# 02-MCU.net
KiCad netlist of a schematic drawn in Altium Designer
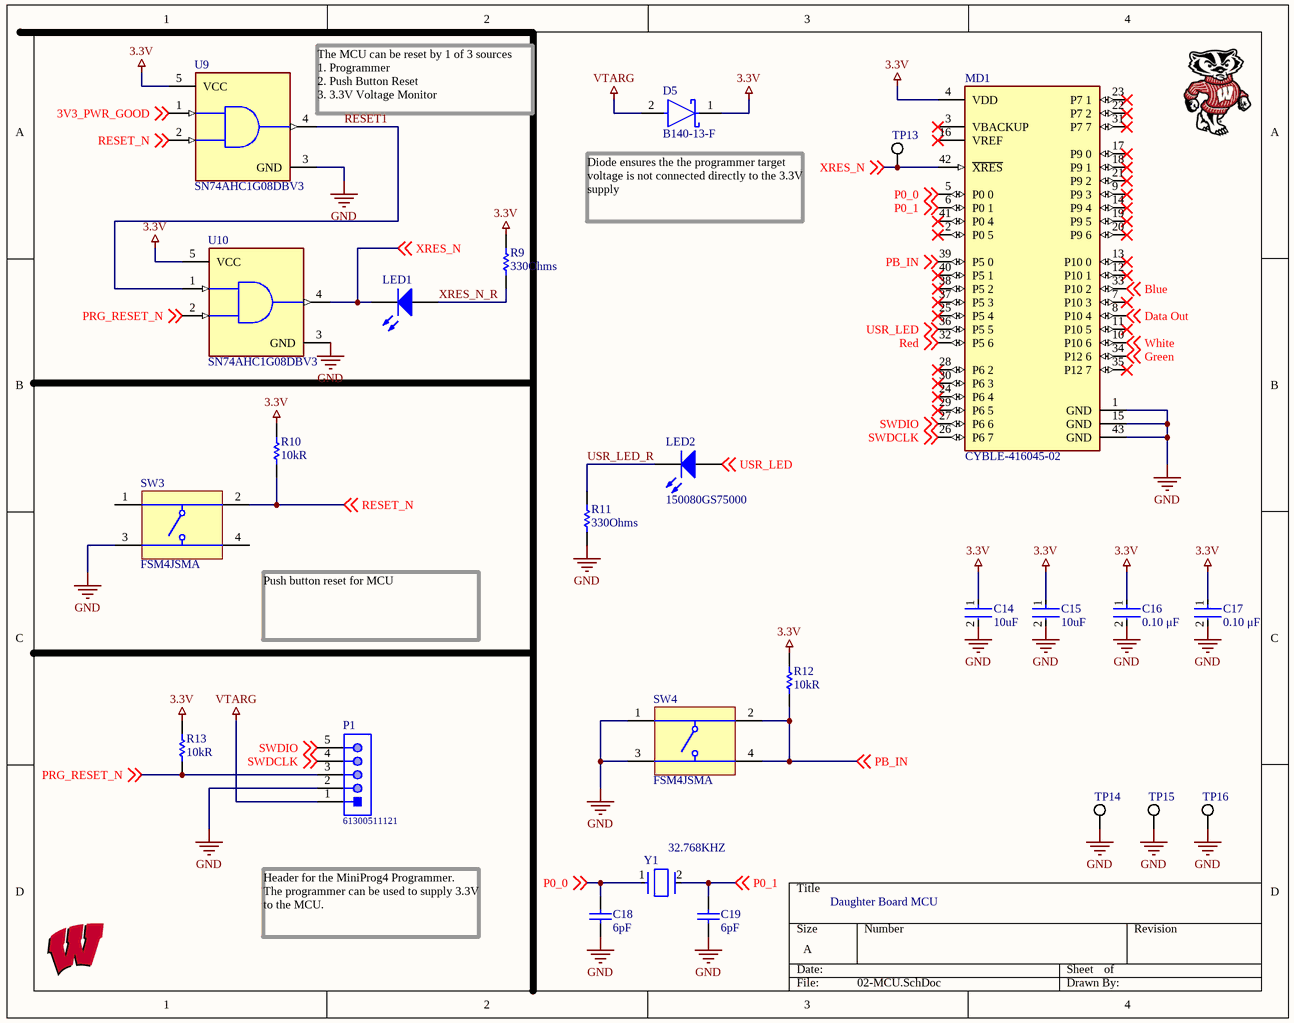
[diagram p0: 02-MCU.SchDoc]

(export (version "E")
  (design (tool "Eeschema 10.0.6"))
  (components
    (comp (ref "C14")
      (value "10uF")
      (footprint "FP-C0805C-DG-MFG")
      (description "CAP CER 10UF 10V X5R 0805")
      (fields (field (name "TOLERANCE") "10%") (field (name "MANUFACTURER PART NUMBER") "C0805C106K8PACTU"))
      (libsource (lib "Altium Content Vault") (part "11868f565c42a9108669ba33697ecf6"))
    )
    (comp (ref "C15")
      (value "10uF")
      (footprint "FP-C0805C-DG-MFG")
      (description "CAP CER 10UF 10V X5R 0805")
      (fields (field (name "TOLERANCE") "10%") (field (name "MANUFACTURER PART NUMBER") "C0805C106K8PACTU"))
      (libsource (lib "Altium Content Vault") (part "11868f565c42a9108669ba33697ecf6"))
    )
    (comp (ref "C16")
      (value "0.10 μF")
      (footprint "FP-C0805C-DN-MFG")
      (description "CAP CER 0.1UF 50V X7R 0805")
      (fields
        (field (name "MANUFACTURER PART NUMBER") "C0805C104K5RACTU")
        (field (name "MANUFACTURER") "KEMET")
      )
      (libsource (lib "Altium Content Vault") (part "b4654b650e69147ec39a6b967a45e02"))
    )
    (comp (ref "C17")
      (value "0.10 μF")
      (footprint "FP-C0805C-DN-MFG")
      (description "CAP CER 0.1UF 50V X7R 0805")
      (fields
        (field (name "MANUFACTURER PART NUMBER") "C0805C104K5RACTU")
        (field (name "MANUFACTURER") "KEMET")
      )
      (libsource (lib "Altium Content Vault") (part "b4654b650e69147ec39a6b967a45e02"))
    )
    (comp (ref "C18")
      (value "08055A6R0CAT2A")
      (footprint "CAPC2013X94X50LL20T25")
      (fields (field (name "MANUFACTURER") "AVX Interconnect / Elco") (field (name "CAPACITANCE") "6pF"))
      (libsource (lib "Altium Content Vault") (part "CAP"))
    )
    (comp (ref "C19")
      (value "08055A6R0CAT2A")
      (footprint "CAPC2013X94X50LL20T25")
      (fields (field (name "MANUFACTURER") "AVX Interconnect / Elco") (field (name "CAPACITANCE") "6pF"))
      (libsource (lib "Altium Content Vault") (part "CAP"))
    )
    (comp (ref "D5")
      (value "B140-13-F")
      (footprint "FP-SMA-MFG")
      (description "DIODE SCHOTTKY 40V 1A SMA")
      (libsource (lib "Altium Content Vault") (part "1d6ec82d83fb6aee721767c19dac4b9"))
    )
    (comp (ref "LED1")
      (value "150080RS75000")
      (footprint "0805_A")
      (description "SMD mono-color Chip LED, WL-SMCW, Red")
      (fields (field (name "MANUFACTURER") "Wuerth Elektronik"))
      (libsource (lib "Altium Content Vault") (part "WE-LED_K1A2-2"))
    )
    (comp (ref "LED2")
      (value "150080GS75000")
      (footprint "0805_A")
      (description "SMD mono-color Chip LED, WL-SMCW, Green")
      (fields (field (name "MANUFACTURER") "Wuerth Elektronik"))
      (libsource (lib "Altium Content Vault") (part "WE-LED_K1A2-2"))
    )
    (comp (ref "MD1")
      (value "CYBLE-416045-02")
      (footprint "FP-CYBLE-416045-02-MFG")
      (description "RF TXRX MOD BLUETOOTH TRACE ANT")
      (fields
        (field (name "OCTOPART") "https://octopart.com/cyble-416045-02-cypress+semiconductor-96386825")
        (field (name "MANUFACTURER") "Cypress Semiconductor")
      )
      (libsource (lib "Altium Content Vault") (part "10a29a4e77099fbb6f911efb04878b1"))
    )
    (comp (ref "P1")
      (value "61300511121")
      (footprint "61300511121")
      (description "THT Vertical Pin Header WR-PHD, Pitch 2.54 mm, Single Row, 5 pins")
      (fields (field (name "MANUFACTURER") "Wurth Elektronik") (field (name "PUBLISHER") "WurthElektronik"))
      (libsource (lib "Altium Content Vault") (part "WE-CN-1P-M-R5"))
    )
    (comp (ref "R9")
      (value "RC0805FR-07330RL")
      (footprint "RESC2013X60X35LL10T20")
      (description "Chip Resistor, 330 Ohm, +/- 1%, 125 mW, -55 to 155 degC, 0805 (2012 Metric), RoHS, Tape and Reel")
      (fields
        (field (name "MANUFACTURER") "Yageo")
        (field (name "TOLERANCE") "1%")
        (field (name "RESISTANCE") "330Ohms")
      )
      (libsource (lib "Altium Content Vault") (part "RES-2"))
    )
    (comp (ref "R10")
      (value "RC0805FR-0710KL")
      (footprint "RESC2013X60X35NL10T20")
      (description "Chip Resistor, 10 KOhm, +/- 1%, 0.125 W, -55 to 155 degC, 0805 (2012 Metric), RoHS, Tape and Reel")
      (fields
        (field (name "MANUFACTURER") "Yageo")
        (field (name "RESISTANCE") "10kR")
        (field (name "TOLERANCE") "1%")
      )
      (libsource (lib "Altium Content Vault") (part "RES-2"))
    )
    (comp (ref "R11")
      (value "RC0805FR-07330RL")
      (footprint "RESC2013X60X35LL10T20")
      (description "Chip Resistor, 330 Ohm, +/- 1%, 125 mW, -55 to 155 degC, 0805 (2012 Metric), RoHS, Tape and Reel")
      (fields
        (field (name "MANUFACTURER") "Yageo")
        (field (name "TOLERANCE") "1%")
        (field (name "RESISTANCE") "330Ohms")
      )
      (libsource (lib "Altium Content Vault") (part "RES-2"))
    )
    (comp (ref "R12")
      (value "RC0805FR-0710KL")
      (footprint "RESC2013X60X35NL10T20")
      (description "Chip Resistor, 10 KOhm, +/- 1%, 0.125 W, -55 to 155 degC, 0805 (2012 Metric), RoHS, Tape and Reel")
      (fields
        (field (name "MANUFACTURER") "Yageo")
        (field (name "RESISTANCE") "10kR")
        (field (name "TOLERANCE") "1%")
      )
      (libsource (lib "Altium Content Vault") (part "RES-2"))
    )
    (comp (ref "R13")
      (value "RC0805FR-0710KL")
      (footprint "RESC2013X60X35NL10T20")
      (description "Chip Resistor, 10 KOhm, +/- 1%, 0.125 W, -55 to 155 degC, 0805 (2012 Metric), RoHS, Tape and Reel")
      (fields
        (field (name "MANUFACTURER") "Yageo")
        (field (name "RESISTANCE") "10kR")
        (field (name "TOLERANCE") "1%")
      )
      (libsource (lib "Altium Content Vault") (part "RES-2"))
    )
    (comp (ref "SW3")
      (value "FSM4JSMA")
      (footprint "TECO-FSM4JSMA_V")
      (description "Swicth, SPST, 24 V, -35 to 85 degC, 4-Pin SMD, RoHS, Tape and Reel")
      (fields (field (name "MANUFACTURER") "TE Connectivity"))
      (libsource (lib "Altium Content Vault") (part "SW-SPST-4_A"))
    )
    (comp (ref "SW4")
      (value "FSM4JSMA")
      (footprint "TECO-FSM4JSMA_V")
      (description "Swicth, SPST, 24 V, -35 to 85 degC, 4-Pin SMD, RoHS, Tape and Reel")
      (fields (field (name "MANUFACTURER") "TE Connectivity"))
      (libsource (lib "Altium Content Vault") (part "SW-SPST-4_A"))
    )
    (comp (ref "TP13")
      (value "5019")
      (footprint "KSTN-5019_V")
      (description "Test Point, 1 Position SMD, RoHS, Tape and Reel")
      (libsource (lib "Altium Content Vault") (part "TESTPOINT_WHITE"))
    )
    (comp (ref "TP14")
      (value "5019")
      (footprint "KSTN-5019_V")
      (description "Test Point, 1 Position SMD, RoHS, Tape and Reel")
      (libsource (lib "Altium Content Vault") (part "TESTPOINT_WHITE"))
    )
    (comp (ref "TP15")
      (value "5019")
      (footprint "KSTN-5019_V")
      (description "Test Point, 1 Position SMD, RoHS, Tape and Reel")
      (libsource (lib "Altium Content Vault") (part "TESTPOINT_WHITE"))
    )
    (comp (ref "TP16")
      (value "5019")
      (footprint "KSTN-5019_V")
      (description "Test Point, 1 Position SMD, RoHS, Tape and Reel")
      (libsource (lib "Altium Content Vault") (part "TESTPOINT_WHITE"))
    )
    (comp (ref "U9")
      (value "SN74AHC1G08DBV3")
      (footprint "FP-DBV0005A-IPC_C")
      (description "IC GATE AND 1CH 2-INP SOT23-5")
      (libsource (lib "Altium Content Vault") (part "675e79b427d6219a5295bf943425e1c"))
    )
    (comp (ref "U10")
      (value "SN74AHC1G08DBV3")
      (footprint "FP-DBV0005A-IPC_C")
      (description "IC GATE AND 1CH 2-INP SOT23-5")
      (libsource (lib "Altium Content Vault") (part "675e79b427d6219a5295bf943425e1c"))
    )
    (comp (ref "Y1")
      (value "32.768KHZ")
      (footprint "FP-ABS07-120-MFG")
      (description "CRYSTAL 32.7680KHZ 6PF SMD")
      (fields (field (name "TOLERANCE") "20ppm"))
      (libsource (lib "Altium Content Vault") (part "c23a69dc6c9e2f18f2079038eb95dd1"))
    )
  )
  (nets
    (net (code "1") (name "/RESET1") (class "Default")
      (node (ref "U10") (pin "1") (pinfunction "A_1") (pintype "input"))
      (node (ref "U9") (pin "4") (pinfunction "Y_4") (pintype "output"))
    )
    (net (code "2") (name "/USR_LED_R") (class "Default")
      (node (ref "LED2") (pin "1") (pinfunction "K_1") (pintype "passive"))
      (node (ref "R11") (pin "2") (pinfunction "2_2") (pintype "passive"))
    )
    (net (code "3") (name "/XRES_N_R") (class "Default")
      (node (ref "LED1") (pin "2") (pinfunction "A_2") (pintype "passive"))
      (node (ref "R9") (pin "1") (pinfunction "1_1") (pintype "passive"))
    )
    (net (code "4") (name "3.3V") (class "Default")
      (node (ref "C14") (pin "1") (pinfunction "1_1") (pintype "passive"))
      (node (ref "C15") (pin "1") (pinfunction "1_1") (pintype "passive"))
      (node (ref "C16") (pin "1") (pinfunction "1_1") (pintype "passive"))
      (node (ref "C17") (pin "1") (pinfunction "1_1") (pintype "passive"))
      (node (ref "D5") (pin "1") (pinfunction "C_1") (pintype "passive"))
      (node (ref "MD1") (pin "4") (pinfunction "VDD_4") (pintype "power_in"))
      (node (ref "R10") (pin "2") (pinfunction "2_2") (pintype "passive"))
      (node (ref "R12") (pin "2") (pinfunction "2_2") (pintype "passive"))
      (node (ref "R13") (pin "2") (pinfunction "2_2") (pintype "passive"))
      (node (ref "R9") (pin "2") (pinfunction "2_2") (pintype "passive"))
      (node (ref "U10") (pin "5") (pinfunction "VCC_5") (pintype "power_in"))
      (node (ref "U9") (pin "5") (pinfunction "VCC_5") (pintype "power_in"))
    )
    (net (code "5") (name "3V3_PWR_GOOD") (class "Default")
      (node (ref "U9") (pin "1") (pinfunction "A_1") (pintype "input"))
    )
    (net (code "6") (name "Blue") (class "Default")
      (node (ref "MD1") (pin "33") (pinfunction "P10_2_33") (pintype "bidirectional"))
    )
    (net (code "7") (name "Data Out") (class "Default")
      (node (ref "MD1") (pin "8") (pinfunction "P10_4_8") (pintype "bidirectional"))
    )
    (net (code "8") (name "GND") (class "Default")
      (node (ref "C14") (pin "2") (pinfunction "2_2") (pintype "passive"))
      (node (ref "C15") (pin "2") (pinfunction "2_2") (pintype "passive"))
      (node (ref "C16") (pin "2") (pinfunction "2_2") (pintype "passive"))
      (node (ref "C17") (pin "2") (pinfunction "2_2") (pintype "passive"))
      (node (ref "C18") (pin "1") (pinfunction "1_1") (pintype "passive"))
      (node (ref "C19") (pin "1") (pinfunction "1_1") (pintype "passive"))
      (node (ref "MD1") (pin "1") (pinfunction "GND_1") (pintype "power_in"))
      (node (ref "MD1") (pin "15") (pinfunction "GND_15") (pintype "power_in"))
      (node (ref "MD1") (pin "43") (pinfunction "GND_43") (pintype "power_in"))
      (node (ref "P1") (pin "2") (pinfunction "2_2") (pintype "passive"))
      (node (ref "R11") (pin "1") (pinfunction "1_1") (pintype "passive"))
      (node (ref "SW3") (pin "3") (pinfunction "3_3") (pintype "passive"))
      (node (ref "SW4") (pin "1") (pinfunction "1_1") (pintype "passive"))
      (node (ref "SW4") (pin "3") (pinfunction "3_3") (pintype "passive"))
      (node (ref "TP14") (pin "1") (pinfunction "1_1") (pintype "passive"))
      (node (ref "TP15") (pin "1") (pinfunction "1_1") (pintype "passive"))
      (node (ref "TP16") (pin "1") (pinfunction "1_1") (pintype "passive"))
      (node (ref "U10") (pin "3") (pinfunction "GND_3") (pintype "power_in"))
      (node (ref "U9") (pin "3") (pinfunction "GND_3") (pintype "power_in"))
    )
    (net (code "9") (name "Green") (class "Default")
      (node (ref "MD1") (pin "34") (pinfunction "P12_6_34") (pintype "bidirectional"))
    )
    (net (code "10") (name "P0_0") (class "Default")
      (node (ref "C18") (pin "2") (pinfunction "2_2") (pintype "passive"))
      (node (ref "MD1") (pin "5") (pinfunction "P0_0_5") (pintype "bidirectional"))
      (node (ref "Y1") (pin "1") (pinfunction "1_1") (pintype "passive"))
    )
    (net (code "11") (name "P0_1") (class "Default")
      (node (ref "C19") (pin "2") (pinfunction "2_2") (pintype "passive"))
      (node (ref "MD1") (pin "6") (pinfunction "P0_1_6") (pintype "bidirectional"))
      (node (ref "Y1") (pin "2") (pinfunction "2_2") (pintype "passive"))
    )
    (net (code "12") (name "PB_IN") (class "Default")
      (node (ref "MD1") (pin "39") (pinfunction "P5_0_39") (pintype "bidirectional"))
      (node (ref "R12") (pin "1") (pinfunction "1_1") (pintype "passive"))
      (node (ref "SW4") (pin "2") (pinfunction "2_2") (pintype "passive"))
      (node (ref "SW4") (pin "4") (pinfunction "4_4") (pintype "passive"))
    )
    (net (code "13") (name "PRG_RESET_N") (class "Default")
      (node (ref "P1") (pin "3") (pinfunction "3_3") (pintype "passive"))
      (node (ref "R13") (pin "1") (pinfunction "1_1") (pintype "passive"))
      (node (ref "U10") (pin "2") (pinfunction "B_2") (pintype "input"))
    )
    (net (code "14") (name "RESET_N") (class "Default")
      (node (ref "R10") (pin "1") (pinfunction "1_1") (pintype "passive"))
      (node (ref "SW3") (pin "2") (pinfunction "2_2") (pintype "passive"))
      (node (ref "U9") (pin "2") (pinfunction "B_2") (pintype "input"))
    )
    (net (code "15") (name "Red") (class "Default")
      (node (ref "MD1") (pin "32") (pinfunction "P5_6_32") (pintype "bidirectional"))
    )
    (net (code "16") (name "SWDCLK") (class "Default")
      (node (ref "MD1") (pin "26") (pinfunction "P6_7_26") (pintype "bidirectional"))
      (node (ref "P1") (pin "4") (pinfunction "4_4") (pintype "passive"))
    )
    (net (code "17") (name "SWDIO") (class "Default")
      (node (ref "MD1") (pin "27") (pinfunction "P6_6_27") (pintype "bidirectional"))
      (node (ref "P1") (pin "5") (pinfunction "5_5") (pintype "passive"))
    )
    (net (code "18") (name "USR_LED") (class "Default")
      (node (ref "LED2") (pin "2") (pinfunction "A_2") (pintype "passive"))
      (node (ref "MD1") (pin "36") (pinfunction "P5_5_36") (pintype "bidirectional"))
    )
    (net (code "19") (name "VTARG") (class "Default")
      (node (ref "D5") (pin "2") (pinfunction "A_2") (pintype "passive"))
      (node (ref "P1") (pin "1") (pinfunction "1_1") (pintype "passive"))
    )
    (net (code "20") (name "White") (class "Default")
      (node (ref "MD1") (pin "10") (pinfunction "P10_6_10") (pintype "bidirectional"))
    )
    (net (code "21") (name "XRES_N") (class "Default")
      (node (ref "LED1") (pin "1") (pinfunction "K_1") (pintype "passive"))
      (node (ref "MD1") (pin "42") (pinfunction "~{XRES}_42") (pintype "input"))
      (node (ref "TP13") (pin "1") (pinfunction "1_1") (pintype "passive"))
      (node (ref "U10") (pin "4") (pinfunction "Y_4") (pintype "output"))
    )
    (net (code "22") (name "unconnected-(MD1-P0_4-Pad41)") (class "Default")
      (node (ref "MD1") (pin "41") (pinfunction "P0_4_41") (pintype "bidirectional+no_connect"))
    )
    (net (code "23") (name "unconnected-(MD1-P0_5-Pad2)") (class "Default")
      (node (ref "MD1") (pin "2") (pinfunction "P0_5_2") (pintype "bidirectional+no_connect"))
    )
    (net (code "24") (name "unconnected-(MD1-P5_1-Pad40)") (class "Default")
      (node (ref "MD1") (pin "40") (pinfunction "P5_1_40") (pintype "bidirectional+no_connect"))
    )
    (net (code "25") (name "unconnected-(MD1-P5_2-Pad38)") (class "Default")
      (node (ref "MD1") (pin "38") (pinfunction "P5_2_38") (pintype "bidirectional+no_connect"))
    )
    (net (code "26") (name "unconnected-(MD1-P5_3-Pad37)") (class "Default")
      (node (ref "MD1") (pin "37") (pinfunction "P5_3_37") (pintype "bidirectional+no_connect"))
    )
    (net (code "27") (name "unconnected-(MD1-P5_4-Pad25)") (class "Default")
      (node (ref "MD1") (pin "25") (pinfunction "P5_4_25") (pintype "bidirectional+no_connect"))
    )
    (net (code "28") (name "unconnected-(MD1-P6_2-Pad28)") (class "Default")
      (node (ref "MD1") (pin "28") (pinfunction "P6_2_28") (pintype "bidirectional+no_connect"))
    )
    (net (code "29") (name "unconnected-(MD1-P6_3-Pad30)") (class "Default")
      (node (ref "MD1") (pin "30") (pinfunction "P6_3_30") (pintype "bidirectional+no_connect"))
    )
    (net (code "30") (name "unconnected-(MD1-P6_4-Pad24)") (class "Default")
      (node (ref "MD1") (pin "24") (pinfunction "P6_4_24") (pintype "bidirectional+no_connect"))
    )
    (net (code "31") (name "unconnected-(MD1-P6_5-Pad29)") (class "Default")
      (node (ref "MD1") (pin "29") (pinfunction "P6_5_29") (pintype "bidirectional+no_connect"))
    )
    (net (code "32") (name "unconnected-(MD1-P7_1-Pad23)") (class "Default")
      (node (ref "MD1") (pin "23") (pinfunction "P7_1_23") (pintype "bidirectional+no_connect"))
    )
    (net (code "33") (name "unconnected-(MD1-P7_2-Pad22)") (class "Default")
      (node (ref "MD1") (pin "22") (pinfunction "P7_2_22") (pintype "bidirectional+no_connect"))
    )
    (net (code "34") (name "unconnected-(MD1-P7_7-Pad31)") (class "Default")
      (node (ref "MD1") (pin "31") (pinfunction "P7_7_31") (pintype "bidirectional+no_connect"))
    )
    (net (code "35") (name "unconnected-(MD1-P9_0-Pad17)") (class "Default")
      (node (ref "MD1") (pin "17") (pinfunction "P9_0_17") (pintype "bidirectional+no_connect"))
    )
    (net (code "36") (name "unconnected-(MD1-P9_1-Pad18)") (class "Default")
      (node (ref "MD1") (pin "18") (pinfunction "P9_1_18") (pintype "bidirectional+no_connect"))
    )
    (net (code "37") (name "unconnected-(MD1-P9_2-Pad21)") (class "Default")
      (node (ref "MD1") (pin "21") (pinfunction "P9_2_21") (pintype "bidirectional+no_connect"))
    )
    (net (code "38") (name "unconnected-(MD1-P9_3-Pad9)") (class "Default")
      (node (ref "MD1") (pin "9") (pinfunction "P9_3_9") (pintype "bidirectional+no_connect"))
    )
    (net (code "39") (name "unconnected-(MD1-P9_4-Pad14)") (class "Default")
      (node (ref "MD1") (pin "14") (pinfunction "P9_4_14") (pintype "bidirectional+no_connect"))
    )
    (net (code "40") (name "unconnected-(MD1-P9_5-Pad19)") (class "Default")
      (node (ref "MD1") (pin "19") (pinfunction "P9_5_19") (pintype "bidirectional+no_connect"))
    )
    (net (code "41") (name "unconnected-(MD1-P9_6-Pad20)") (class "Default")
      (node (ref "MD1") (pin "20") (pinfunction "P9_6_20") (pintype "bidirectional+no_connect"))
    )
    (net (code "42") (name "unconnected-(MD1-P10_0-Pad13)") (class "Default")
      (node (ref "MD1") (pin "13") (pinfunction "P10_0_13") (pintype "bidirectional+no_connect"))
    )
    (net (code "43") (name "unconnected-(MD1-P10_1-Pad12)") (class "Default")
      (node (ref "MD1") (pin "12") (pinfunction "P10_1_12") (pintype "bidirectional+no_connect"))
    )
    (net (code "44") (name "unconnected-(MD1-P10_3-Pad7)") (class "Default")
      (node (ref "MD1") (pin "7") (pinfunction "P10_3_7") (pintype "bidirectional+no_connect"))
    )
    (net (code "45") (name "unconnected-(MD1-P10_5-Pad11)") (class "Default")
      (node (ref "MD1") (pin "11") (pinfunction "P10_5_11") (pintype "bidirectional+no_connect"))
    )
    (net (code "46") (name "unconnected-(MD1-P12_7-Pad35)") (class "Default")
      (node (ref "MD1") (pin "35") (pinfunction "P12_7_35") (pintype "bidirectional+no_connect"))
    )
    (net (code "47") (name "unconnected-(MD1-VBACKUP-Pad3)") (class "Default")
      (node (ref "MD1") (pin "3") (pinfunction "VBACKUP_3") (pintype "power_in+no_connect"))
    )
    (net (code "48") (name "unconnected-(MD1-VREF-Pad16)") (class "Default")
      (node (ref "MD1") (pin "16") (pinfunction "VREF_16") (pintype "power_in+no_connect"))
    )
    (net (code "49") (name "unconnected-(SW3-Pad1)") (class "Default")
      (node (ref "SW3") (pin "1") (pinfunction "1_1") (pintype "passive"))
    )
    (net (code "50") (name "unconnected-(SW3-Pad4)") (class "Default")
      (node (ref "SW3") (pin "4") (pinfunction "4_4") (pintype "passive"))
    )
  )
)
